# rhd2132.net
KiCad netlist of a schematic drawn in Altium Designer
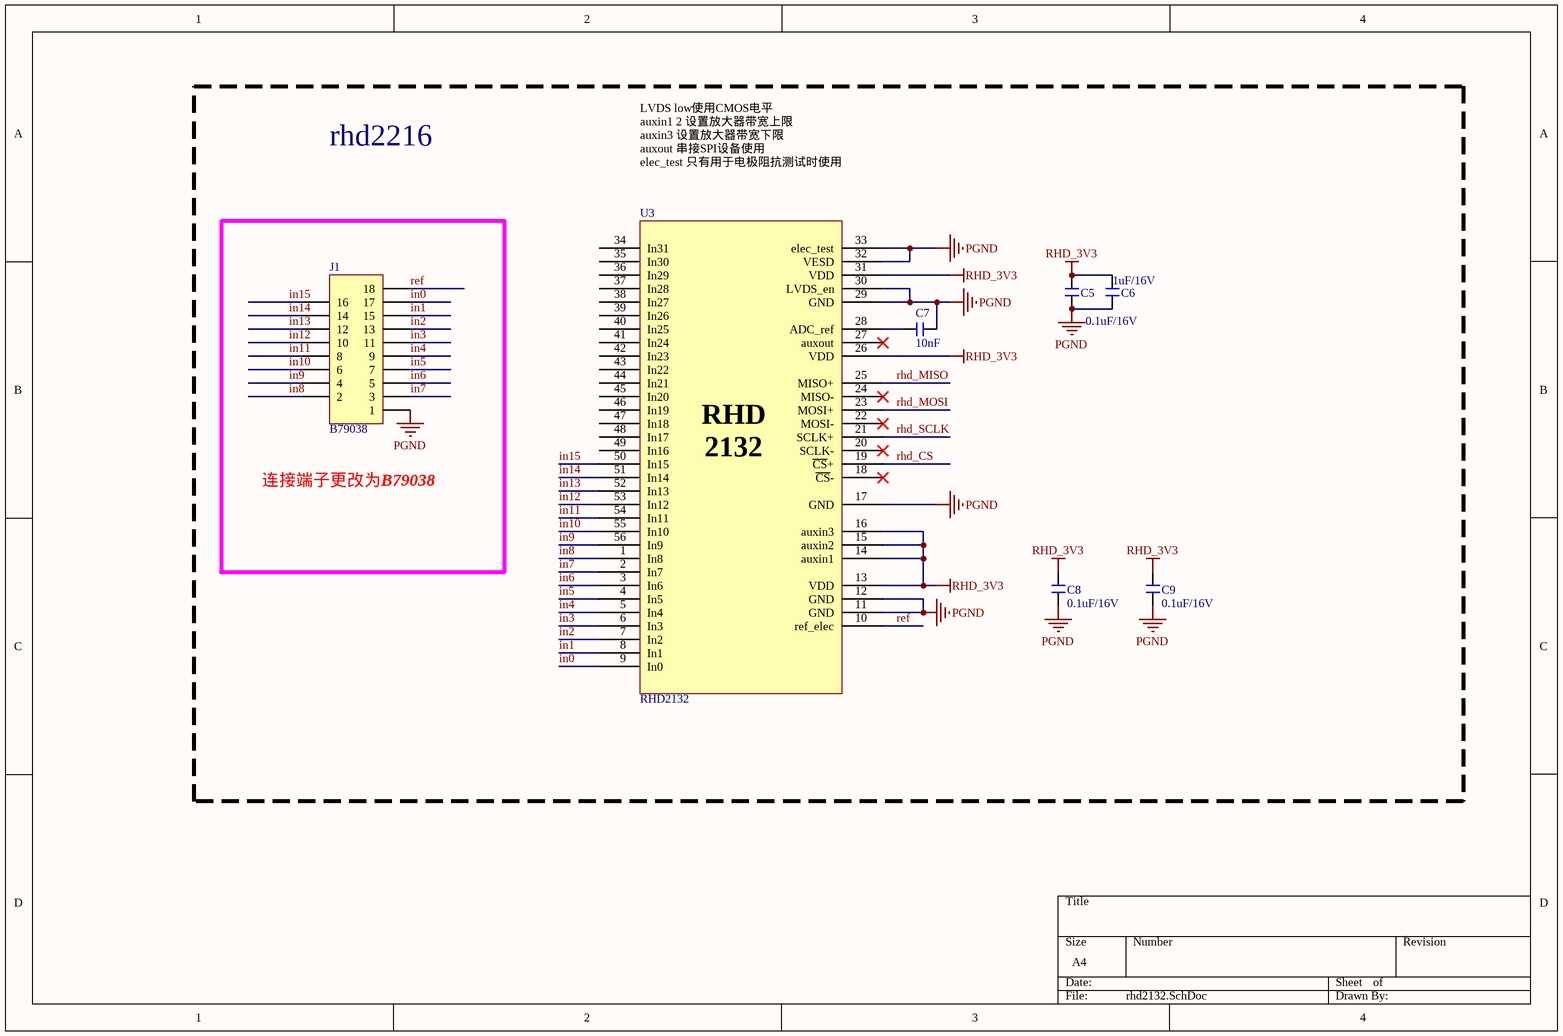
[diagram p0: rhd2132.SchDoc]

(export (version "E")
  (design (tool "Eeschema 10.0.6"))
  (components
    (comp (ref "C5")
      (value "0.1uF/16V")
      (footprint "C 0201_L")
      (description "贴片电容")
      (libsource (lib "0.1 - 电阻-电容-电感") (part "C"))
    )
    (comp (ref "C6")
      (value "1uF/16V")
      (footprint "C 0201_L")
      (description "贴片电容")
      (libsource (lib "0.1 - 电阻-电容-电感") (part "C"))
    )
    (comp (ref "C7")
      (value "10nF")
      (footprint "C 0201_L")
      (description "贴片电容")
      (libsource (lib "0.1 - 电阻-电容-电感") (part "C"))
    )
    (comp (ref "C8")
      (value "0.1uF/16V")
      (footprint "C 0201_L")
      (description "贴片电容")
      (libsource (lib "0.1 - 电阻-电容-电感") (part "C"))
    )
    (comp (ref "C9")
      (value "0.1uF/16V")
      (footprint "C 0201_L")
      (description "贴片电容")
      (libsource (lib "0.1 - 电阻-电容-电感") (part "C"))
    )
    (comp (ref "J1")
      (value "B79038")
      (footprint "B79038")
      (fields (field (name "PUBLISHER") "Altium Limited"))
      (libsource (lib "ZJBCI_LIB") (part "CON_A79015-001-18PIN"))
    )
    (comp (ref "U3") (value "RHD2132") (footprint "QFN-56-9mm") (libsource (lib "rhd2216") (part "RHD2132")))
  )
  (nets
    (net (code "1") (name "/in0") (class "Default")
      (node (ref "J1") (pin "17") (pinfunction "17_17") (pintype "passive"))
      (node (ref "U3") (pin "9") (pinfunction "In0_9") (pintype "passive"))
    )
    (net (code "2") (name "/in1") (class "Default")
      (node (ref "J1") (pin "15") (pinfunction "15_15") (pintype "passive"))
      (node (ref "U3") (pin "8") (pinfunction "In1_8") (pintype "passive"))
    )
    (net (code "3") (name "/in2") (class "Default")
      (node (ref "J1") (pin "13") (pinfunction "13_13") (pintype "passive"))
      (node (ref "U3") (pin "7") (pinfunction "In2_7") (pintype "passive"))
    )
    (net (code "4") (name "/in3") (class "Default")
      (node (ref "J1") (pin "11") (pinfunction "11_11") (pintype "passive"))
      (node (ref "U3") (pin "6") (pinfunction "In3_6") (pintype "passive"))
    )
    (net (code "5") (name "/in4") (class "Default")
      (node (ref "J1") (pin "9") (pinfunction "9_9") (pintype "passive"))
      (node (ref "U3") (pin "5") (pinfunction "In4_5") (pintype "passive"))
    )
    (net (code "6") (name "/in5") (class "Default")
      (node (ref "J1") (pin "7") (pinfunction "7_7") (pintype "passive"))
      (node (ref "U3") (pin "4") (pinfunction "In5_4") (pintype "passive"))
    )
    (net (code "7") (name "/in6") (class "Default")
      (node (ref "J1") (pin "5") (pinfunction "5_5") (pintype "passive"))
      (node (ref "U3") (pin "3") (pinfunction "In6_3") (pintype "passive"))
    )
    (net (code "8") (name "/in7") (class "Default")
      (node (ref "J1") (pin "3") (pinfunction "3_3") (pintype "passive"))
      (node (ref "U3") (pin "2") (pinfunction "In7_2") (pintype "passive"))
    )
    (net (code "9") (name "/in8") (class "Default")
      (node (ref "J1") (pin "2") (pinfunction "2_2") (pintype "passive"))
      (node (ref "U3") (pin "1") (pinfunction "In8_1") (pintype "passive"))
    )
    (net (code "10") (name "/in9") (class "Default")
      (node (ref "J1") (pin "4") (pinfunction "4_4") (pintype "passive"))
      (node (ref "U3") (pin "56") (pinfunction "In9_56") (pintype "passive"))
    )
    (net (code "11") (name "/in10") (class "Default")
      (node (ref "J1") (pin "6") (pinfunction "6_6") (pintype "passive"))
      (node (ref "U3") (pin "55") (pinfunction "In10_55") (pintype "passive"))
    )
    (net (code "12") (name "/in11") (class "Default")
      (node (ref "J1") (pin "8") (pinfunction "8_8") (pintype "passive"))
      (node (ref "U3") (pin "54") (pinfunction "In11_54") (pintype "passive"))
    )
    (net (code "13") (name "/in12") (class "Default")
      (node (ref "J1") (pin "10") (pinfunction "10_10") (pintype "passive"))
      (node (ref "U3") (pin "53") (pinfunction "In12_53") (pintype "passive"))
    )
    (net (code "14") (name "/in13") (class "Default")
      (node (ref "J1") (pin "12") (pinfunction "12_12") (pintype "passive"))
      (node (ref "U3") (pin "52") (pinfunction "In13_52") (pintype "passive"))
    )
    (net (code "15") (name "/in14") (class "Default")
      (node (ref "J1") (pin "14") (pinfunction "14_14") (pintype "passive"))
      (node (ref "U3") (pin "51") (pinfunction "In14_51") (pintype "passive"))
    )
    (net (code "16") (name "/in15") (class "Default")
      (node (ref "J1") (pin "16") (pinfunction "16_16") (pintype "passive"))
      (node (ref "U3") (pin "50") (pinfunction "In15_50") (pintype "passive"))
    )
    (net (code "17") (name "/ref") (class "Default")
      (node (ref "J1") (pin "18") (pinfunction "18_18") (pintype "passive"))
      (node (ref "U3") (pin "10") (pinfunction "ref_elec_10") (pintype "passive"))
    )
    (net (code "18") (name "/rhd_CS") (class "Default")
      (node (ref "U3") (pin "19") (pinfunction "~{CS}+_19") (pintype "passive"))
    )
    (net (code "19") (name "/rhd_MISO") (class "Default")
      (node (ref "U3") (pin "25") (pinfunction "MISO+_25") (pintype "passive"))
    )
    (net (code "20") (name "/rhd_MOSI") (class "Default")
      (node (ref "U3") (pin "23") (pinfunction "MOSI+_23") (pintype "passive"))
    )
    (net (code "21") (name "/rhd_SCLK") (class "Default")
      (node (ref "U3") (pin "21") (pinfunction "SCLK+_21") (pintype "passive"))
    )
    (net (code "22") (name "Net-(U3-ADC_ref)") (class "Default")
      (node (ref "C7") (pin "1") (pinfunction "1_1") (pintype "passive"))
      (node (ref "U3") (pin "28") (pinfunction "ADC_ref_28") (pintype "passive"))
    )
    (net (code "23") (name "PGND") (class "Default")
      (node (ref "C5") (pin "1") (pinfunction "1_1") (pintype "passive"))
      (node (ref "C6") (pin "1") (pinfunction "1_1") (pintype "passive"))
      (node (ref "C7") (pin "2") (pinfunction "2_2") (pintype "passive"))
      (node (ref "C8") (pin "1") (pinfunction "1_1") (pintype "passive"))
      (node (ref "C9") (pin "1") (pinfunction "1_1") (pintype "passive"))
      (node (ref "J1") (pin "1") (pinfunction "1_1") (pintype "passive"))
      (node (ref "U3") (pin "11") (pinfunction "GND_11") (pintype "passive"))
      (node (ref "U3") (pin "12") (pinfunction "GND_12") (pintype "passive"))
      (node (ref "U3") (pin "17") (pinfunction "GND_17") (pintype "passive"))
      (node (ref "U3") (pin "29") (pinfunction "GND_29") (pintype "passive"))
      (node (ref "U3") (pin "30") (pinfunction "LVDS_en_30") (pintype "passive"))
      (node (ref "U3") (pin "32") (pinfunction "VESD_32") (pintype "passive"))
      (node (ref "U3") (pin "33") (pinfunction "elec_test_33") (pintype "passive"))
    )
    (net (code "24") (name "RHD_3V3") (class "Default")
      (node (ref "C5") (pin "2") (pinfunction "2_2") (pintype "passive"))
      (node (ref "C6") (pin "2") (pinfunction "2_2") (pintype "passive"))
      (node (ref "C8") (pin "2") (pinfunction "2_2") (pintype "passive"))
      (node (ref "C9") (pin "2") (pinfunction "2_2") (pintype "passive"))
      (node (ref "U3") (pin "13") (pinfunction "VDD_13") (pintype "passive"))
      (node (ref "U3") (pin "14") (pinfunction "auxin1_14") (pintype "passive"))
      (node (ref "U3") (pin "15") (pinfunction "auxin2_15") (pintype "passive"))
      (node (ref "U3") (pin "16") (pinfunction "auxin3_16") (pintype "passive"))
      (node (ref "U3") (pin "26") (pinfunction "VDD_26") (pintype "passive"))
      (node (ref "U3") (pin "31") (pinfunction "VDD_31") (pintype "passive"))
    )
    (net (code "25") (name "unconnected-(U3-In16-Pad49)") (class "Default")
      (node (ref "U3") (pin "49") (pinfunction "In16_49") (pintype "passive"))
    )
    (net (code "26") (name "unconnected-(U3-In17-Pad48)") (class "Default")
      (node (ref "U3") (pin "48") (pinfunction "In17_48") (pintype "passive"))
    )
    (net (code "27") (name "unconnected-(U3-In18-Pad47)") (class "Default")
      (node (ref "U3") (pin "47") (pinfunction "In18_47") (pintype "passive"))
    )
    (net (code "28") (name "unconnected-(U3-In19-Pad46)") (class "Default")
      (node (ref "U3") (pin "46") (pinfunction "In19_46") (pintype "passive"))
    )
    (net (code "29") (name "unconnected-(U3-In20-Pad45)") (class "Default")
      (node (ref "U3") (pin "45") (pinfunction "In20_45") (pintype "passive"))
    )
    (net (code "30") (name "unconnected-(U3-In21-Pad44)") (class "Default")
      (node (ref "U3") (pin "44") (pinfunction "In21_44") (pintype "passive"))
    )
    (net (code "31") (name "unconnected-(U3-In22-Pad43)") (class "Default")
      (node (ref "U3") (pin "43") (pinfunction "In22_43") (pintype "passive"))
    )
    (net (code "32") (name "unconnected-(U3-In23-Pad42)") (class "Default")
      (node (ref "U3") (pin "42") (pinfunction "In23_42") (pintype "passive"))
    )
    (net (code "33") (name "unconnected-(U3-In24-Pad41)") (class "Default")
      (node (ref "U3") (pin "41") (pinfunction "In24_41") (pintype "passive"))
    )
    (net (code "34") (name "unconnected-(U3-In25-Pad40)") (class "Default")
      (node (ref "U3") (pin "40") (pinfunction "In25_40") (pintype "passive"))
    )
    (net (code "35") (name "unconnected-(U3-In26-Pad39)") (class "Default")
      (node (ref "U3") (pin "39") (pinfunction "In26_39") (pintype "passive"))
    )
    (net (code "36") (name "unconnected-(U3-In27-Pad38)") (class "Default")
      (node (ref "U3") (pin "38") (pinfunction "In27_38") (pintype "passive"))
    )
    (net (code "37") (name "unconnected-(U3-In28-Pad37)") (class "Default")
      (node (ref "U3") (pin "37") (pinfunction "In28_37") (pintype "passive"))
    )
    (net (code "38") (name "unconnected-(U3-In29-Pad36)") (class "Default")
      (node (ref "U3") (pin "36") (pinfunction "In29_36") (pintype "passive"))
    )
    (net (code "39") (name "unconnected-(U3-In30-Pad35)") (class "Default")
      (node (ref "U3") (pin "35") (pinfunction "In30_35") (pintype "passive"))
    )
    (net (code "40") (name "unconnected-(U3-In31-Pad34)") (class "Default")
      (node (ref "U3") (pin "34") (pinfunction "In31_34") (pintype "passive"))
    )
    (net (code "41") (name "unconnected-(U3-MISO--Pad24)") (class "Default")
      (node (ref "U3") (pin "24") (pinfunction "MISO-_24") (pintype "passive+no_connect"))
    )
    (net (code "42") (name "unconnected-(U3-MOSI--Pad22)") (class "Default")
      (node (ref "U3") (pin "22") (pinfunction "MOSI-_22") (pintype "passive+no_connect"))
    )
    (net (code "43") (name "unconnected-(U3-SCLK--Pad20)") (class "Default")
      (node (ref "U3") (pin "20") (pinfunction "SCLK-_20") (pintype "passive+no_connect"))
    )
    (net (code "44") (name "unconnected-(U3-auxout-Pad27)") (class "Default")
      (node (ref "U3") (pin "27") (pinfunction "auxout_27") (pintype "passive+no_connect"))
    )
    (net (code "45") (name "unconnected-(U3-~{CS}--Pad18)") (class "Default")
      (node (ref "U3") (pin "18") (pinfunction "~{CS}-_18") (pintype "passive+no_connect"))
    )
  )
)
